# Sens_BMP180.net
KiCad netlist of a schematic drawn in EAGLE
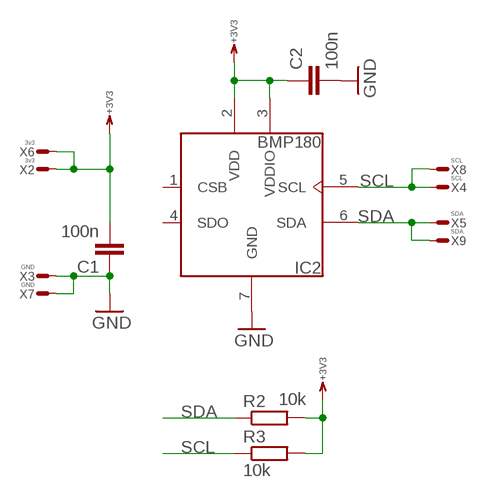
[diagram p0: schematic, sheet 1]

(export (version "E")
  (design (tool "Eeschema 10.0.6"))
  (components
    (comp (ref "C1")
      (value "100n")
      (footprint "eagle-import:0603")
      (libsource (lib "eagle-import") (part "C0603"))
    )
    (comp (ref "C2")
      (value "100n")
      (footprint "eagle-import:0603")
      (libsource (lib "eagle-import") (part "C0603"))
    )
    (comp (ref "IC2")
      (value "BMP180")
      (footprint "eagle-import:7-VELGA")
      (libsource (lib "eagle-import") (part "BMP180"))
    )
    (comp (ref "R2")
      (value "10k")
      (footprint "eagle-import:0603")
      (libsource (lib "eagle-import") (part "R0603"))
    )
    (comp (ref "R3")
      (value "10k")
      (footprint "eagle-import:0603")
      (libsource (lib "eagle-import") (part "R0603"))
    )
    (comp (ref "X2")
      (value "3v3")
      (footprint "eagle-import:T1.6_0.9")
      (libsource (lib "eagle-import") (part "WIREPADT1.6/0.9"))
    )
    (comp (ref "X3")
      (value "GND")
      (footprint "eagle-import:T1.6_0.9")
      (libsource (lib "eagle-import") (part "WIREPADT1.6/0.9"))
    )
    (comp (ref "X4")
      (value "SCL")
      (footprint "eagle-import:T1.6_0.9")
      (libsource (lib "eagle-import") (part "WIREPADT1.6/0.9"))
    )
    (comp (ref "X5")
      (value "SDA")
      (footprint "eagle-import:T1.6_0.9")
      (libsource (lib "eagle-import") (part "WIREPADT1.6/0.9"))
    )
    (comp (ref "X6")
      (value "3v3")
      (footprint "eagle-import:T1.6_0.9")
      (libsource (lib "eagle-import") (part "WIREPADT1.6/0.9"))
    )
    (comp (ref "X7")
      (value "GND")
      (footprint "eagle-import:T1.6_0.9")
      (libsource (lib "eagle-import") (part "WIREPADT1.6/0.9"))
    )
    (comp (ref "X8")
      (value "SCL")
      (footprint "eagle-import:T1.6_0.9")
      (libsource (lib "eagle-import") (part "WIREPADT1.6/0.9"))
    )
    (comp (ref "X9")
      (value "SDA")
      (footprint "eagle-import:T1.6_0.9")
      (libsource (lib "eagle-import") (part "WIREPADT1.6/0.9"))
    )
  )
  (nets
    (net (code "1") (name "+3V3") (class "Default")
      (node (ref "C1") (pin "2") (pinfunction "2_2") (pintype "passive"))
      (node (ref "C2") (pin "1") (pinfunction "1_1") (pintype "passive"))
      (node (ref "IC2") (pin "2") (pinfunction "VDD_2") (pintype "bidirectional"))
      (node (ref "IC2") (pin "3") (pinfunction "VDDIO_3") (pintype "bidirectional"))
      (node (ref "R2") (pin "2") (pinfunction "2_2") (pintype "passive"))
      (node (ref "R3") (pin "2") (pinfunction "2_2") (pintype "passive"))
      (node (ref "X2") (pin "1") (pinfunction "S_1") (pintype "passive"))
      (node (ref "X6") (pin "1") (pinfunction "S_1") (pintype "passive"))
    )
    (net (code "2") (name "/SCL") (class "Default")
      (node (ref "IC2") (pin "5") (pinfunction "SCL_5") (pintype "input"))
      (node (ref "R3") (pin "1") (pinfunction "1_1") (pintype "passive"))
      (node (ref "X4") (pin "1") (pinfunction "S_1") (pintype "passive"))
      (node (ref "X8") (pin "1") (pinfunction "S_1") (pintype "passive"))
    )
    (net (code "3") (name "/SDA") (class "Default")
      (node (ref "IC2") (pin "6") (pinfunction "SDA_6") (pintype "bidirectional"))
      (node (ref "R2") (pin "1") (pinfunction "1_1") (pintype "passive"))
      (node (ref "X5") (pin "1") (pinfunction "S_1") (pintype "passive"))
      (node (ref "X9") (pin "1") (pinfunction "S_1") (pintype "passive"))
    )
    (net (code "4") (name "GND") (class "Default")
      (node (ref "C1") (pin "1") (pinfunction "1_1") (pintype "passive"))
      (node (ref "C2") (pin "2") (pinfunction "2_2") (pintype "passive"))
      (node (ref "IC2") (pin "7") (pinfunction "GND_7") (pintype "bidirectional"))
      (node (ref "X3") (pin "1") (pinfunction "S_1") (pintype "passive"))
      (node (ref "X7") (pin "1") (pinfunction "S_1") (pintype "passive"))
    )
    (net (code "5") (name "unconnected-(IC2-CSB-Pad1)") (class "Default")
      (node (ref "IC2") (pin "1") (pinfunction "CSB_1") (pintype "no_connect"))
    )
    (net (code "6") (name "unconnected-(IC2-SDO-Pad4)") (class "Default")
      (node (ref "IC2") (pin "4") (pinfunction "SDO_4") (pintype "no_connect"))
    )
  )
)
